# 03_-_POWER.net
KiCad netlist of a schematic drawn in Altium Designer
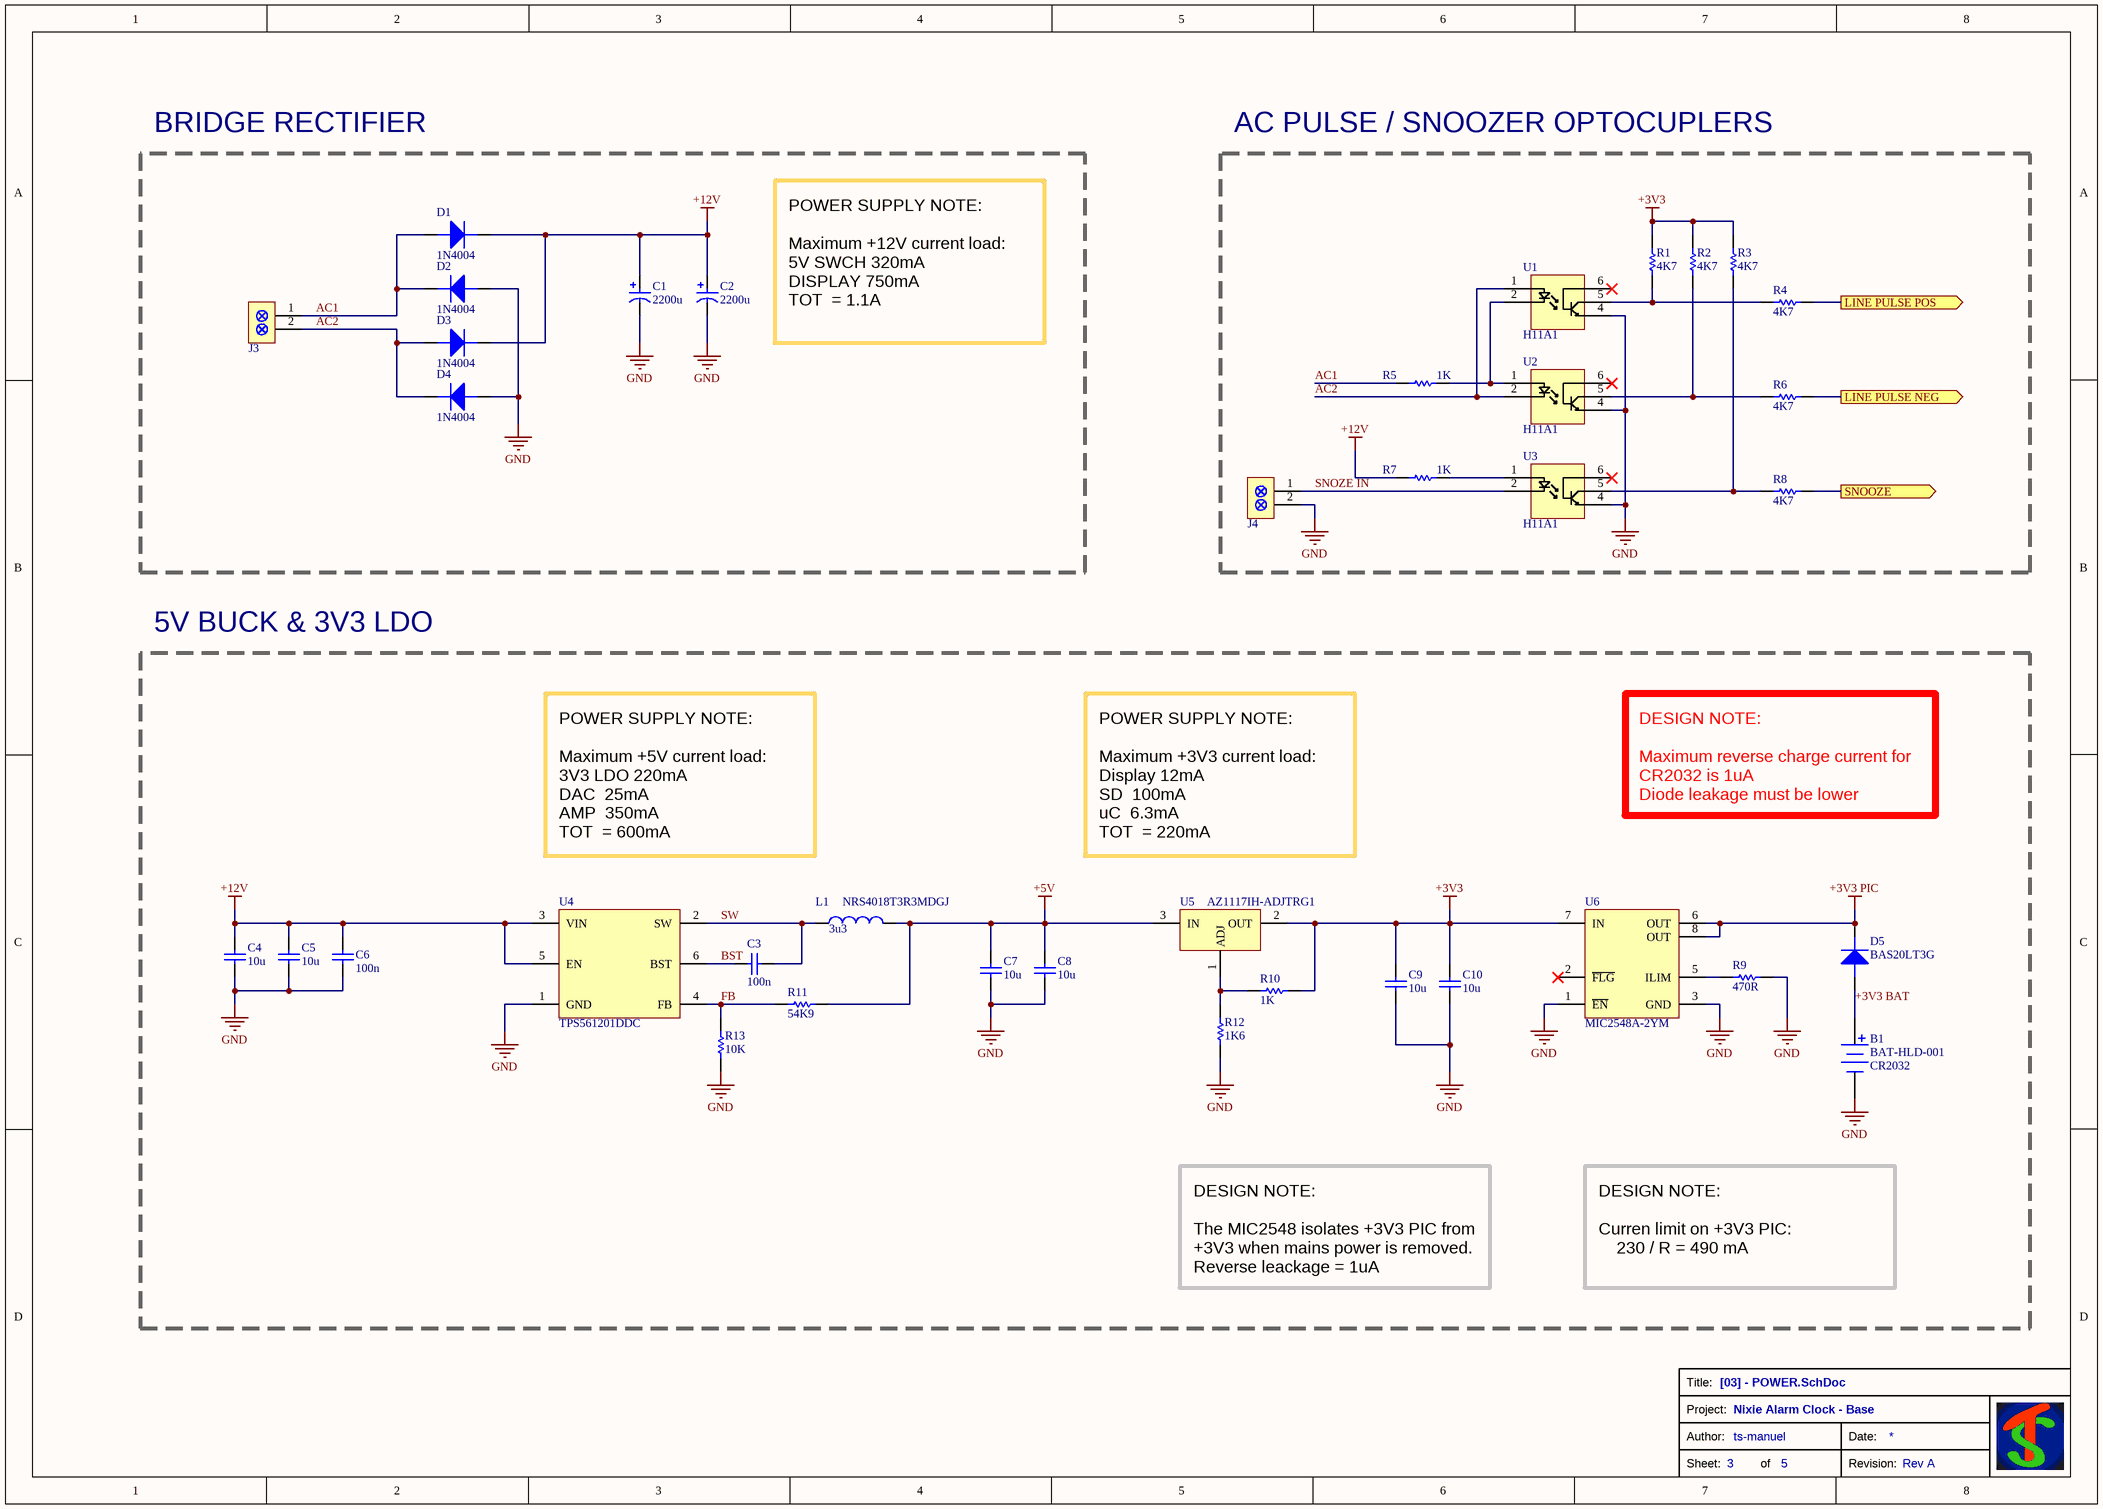
[diagram p0: [03] - POWER.SchDoc]

(export (version "E")
  (design (tool "Eeschema 10.0.6"))
  (components
    (comp (ref "B1")
      (value "BAT-HLD-001")
      (footprint "BATHLD001-CR2032")
      (description "Portabatterie a celle a bottone Linx CR2032 Battery Holder")
      (fields (field (name "SIZE") "CR2032"))
      (libsource (lib "mt_local_library") (part "CR2032-SMD-BAT-HLD-001"))
    )
    (comp (ref "C1")
      (value "2200u")
      (footprint "CAPPRD500W60D1300H2700")
      (description "ALU 25V 2200uF  RippleCurrent=1.3A 20%")
      (fields (field (name "MANUFACTURER") "KEMET") (field (name "TOLERANCE") "20%"))
      (libsource (lib "Passives") (part "CAP-RADIAL-2200u-25V-ALU-20%"))
    )
    (comp (ref "C2")
      (value "2200u")
      (footprint "CAPPRD500W60D1300H2700")
      (description "ALU 25V 2200uF  RippleCurrent=1.3A 20%")
      (fields (field (name "MANUFACTURER") "KEMET") (field (name "TOLERANCE") "20%"))
      (libsource (lib "Passives") (part "CAP-RADIAL-2200u-25V-ALU-20%"))
    )
    (comp (ref "C3")
      (value "100n")
      (footprint "CAP-0603")
      (description "MLCC - SMD 16V 100nF X7R 0603 20%")
      (fields (field (name "TOLERANCE") "20%") (field (name "MANUFACTURER") "KEMET"))
      (libsource (lib "Passives") (part "CAP-0603-100n-16V-X7R-20%"))
    )
    (comp (ref "C4")
      (value "10u")
      (footprint "CAP-0805")
      (description "MLCC - SMD 25V 10uF X5R 10%")
      (fields (field (name "MANUFACTURER") "Samsung") (field (name "TOLERANCE") "10%"))
      (libsource (lib "Passives") (part "CAP-0805-10u-25V-X5R-10%"))
    )
    (comp (ref "C5")
      (value "10u")
      (footprint "CAP-0805")
      (description "MLCC - SMD 25V 10uF X5R 10%")
      (fields (field (name "MANUFACTURER") "Samsung") (field (name "TOLERANCE") "10%"))
      (libsource (lib "Passives") (part "CAP-0805-10u-25V-X5R-10%"))
    )
    (comp (ref "C6")
      (value "100n")
      (footprint "CAP-0603")
      (description "MLCC - SMD 16V 100nF X7R 0603 20%")
      (fields (field (name "TOLERANCE") "20%") (field (name "MANUFACTURER") "KEMET"))
      (libsource (lib "Passives") (part "CAP-0603-100n-16V-X7R-20%"))
    )
    (comp (ref "C7")
      (value "10u")
      (footprint "CAP-0805")
      (description "MLCC - SMD 25V 10uF X5R 10%")
      (fields (field (name "MANUFACTURER") "Samsung") (field (name "TOLERANCE") "10%"))
      (libsource (lib "Passives") (part "CAP-0805-10u-25V-X5R-10%"))
    )
    (comp (ref "C8")
      (value "10u")
      (footprint "CAP-0805")
      (description "MLCC - SMD 25V 10uF X5R 10%")
      (fields (field (name "MANUFACTURER") "Samsung") (field (name "TOLERANCE") "10%"))
      (libsource (lib "Passives") (part "CAP-0805-10u-25V-X5R-10%"))
    )
    (comp (ref "C9")
      (value "10u")
      (footprint "CAP-0805")
      (description "MLCC - SMD 25V 10uF X5R 10%")
      (fields (field (name "MANUFACTURER") "Samsung") (field (name "TOLERANCE") "10%"))
      (libsource (lib "Passives") (part "CAP-0805-10u-25V-X5R-10%"))
    )
    (comp (ref "C10")
      (value "10u")
      (footprint "CAP-0805")
      (description "MLCC - SMD 25V 10uF X5R 10%")
      (fields (field (name "MANUFACTURER") "Samsung") (field (name "TOLERANCE") "10%"))
      (libsource (lib "Passives") (part "CAP-0805-10u-25V-X5R-10%"))
    )
    (comp (ref "D1")
      (value "1N4004")
      (footprint "DIODE-DO41")
      (description "Silicon Diode - 400V 50uA 1A")
      (libsource (lib "mt_local_library") (part "DIODE-1N4004-T"))
    )
    (comp (ref "D2")
      (value "1N4004")
      (footprint "DIODE-DO41")
      (description "Silicon Diode - 400V 50uA 1A")
      (libsource (lib "mt_local_library") (part "DIODE-1N4004-T"))
    )
    (comp (ref "D3")
      (value "1N4004")
      (footprint "DIODE-DO41")
      (description "Silicon Diode - 400V 50uA 1A")
      (libsource (lib "mt_local_library") (part "DIODE-1N4004-T"))
    )
    (comp (ref "D4")
      (value "1N4004")
      (footprint "DIODE-DO41")
      (description "Silicon Diode - 400V 50uA 1A")
      (libsource (lib "mt_local_library") (part "DIODE-1N4004-T"))
    )
    (comp (ref "D5")
      (value "BAS20LT3G")
      (footprint "SOT95P240X110-3N")
      (description "Silicon Diode - 200V 0.1uA 200mA")
      (libsource (lib "mt_local_library") (part "DIODE-BAS20LT3G"))
    )
    (comp (ref "J3")
      (value "SCREW-TH-BLOCK-200-2")
      (footprint "SCREW-TH-BLOCK-200-2")
      (description "Screw Therminal Block 200 mil Pitch 2 Contacts")
      (libsource (lib "mt_local_library") (part "SCREW-TH-BLOCK-200-2"))
    )
    (comp (ref "J4")
      (value "SCREW-TH-BLOCK-200-2")
      (footprint "SCREW-TH-BLOCK-200-2")
      (description "Screw Therminal Block 200 mil Pitch 2 Contacts")
      (libsource (lib "mt_local_library") (part "SCREW-TH-BLOCK-200-2"))
    )
    (comp (ref "L1")
      (value "NRS4018T3R3MDGJ")
      (footprint "INDP4040X18M")
      (description "Fixed Inductor 4018 3.3uH 66mOhms +/-20%Tol 2300mA")
      (fields
        (field (name "MANUFACTURER") "Taiyo Yuden")
        (field (name "TOLERANCE") "20%")
        (field (name "ALTIUM_VALUE") "3u3")
      )
      (libsource (lib "Passives") (part "IND-4018-3u3-NRS4018T3R3MDGJ"))
    )
    (comp (ref "R1")
      (value "4K7")
      (footprint "RES-0603")
      (description "Thick Film - SMD 75V 1/10W 4.7K ohm 0603 1%")
      (fields (field (name "MANUFACTURER") "Yageo") (field (name "TOLERANCE") "1%"))
      (libsource (lib "Passives") (part "RES-0603-4K7-1/10W-1%"))
    )
    (comp (ref "R2")
      (value "4K7")
      (footprint "RES-0603")
      (description "Thick Film - SMD 75V 1/10W 4.7K ohm 0603 1%")
      (fields (field (name "MANUFACTURER") "Yageo") (field (name "TOLERANCE") "1%"))
      (libsource (lib "Passives") (part "RES-0603-4K7-1/10W-1%"))
    )
    (comp (ref "R3")
      (value "4K7")
      (footprint "RES-0603")
      (description "Thick Film - SMD 75V 1/10W 4.7K ohm 0603 1%")
      (fields (field (name "MANUFACTURER") "Yageo") (field (name "TOLERANCE") "1%"))
      (libsource (lib "Passives") (part "RES-0603-4K7-1/10W-1%"))
    )
    (comp (ref "R4")
      (value "4K7")
      (footprint "RES-0603")
      (description "Thick Film - SMD 75V 1/10W 4.7K ohm 0603 1%")
      (fields (field (name "MANUFACTURER") "Yageo") (field (name "TOLERANCE") "1%"))
      (libsource (lib "Passives") (part "RES-0603-4K7-1/10W-1%"))
    )
    (comp (ref "R5")
      (value "1K")
      (footprint "RES-0805")
      (description "Thick Film - SMD 150V 1/8W 1K ohm 0805 1%")
      (fields (field (name "MANUFACTURER") "Yageo") (field (name "TOLERANCE") "1%"))
      (libsource (lib "Passives") (part "RES-0805-1K-1/8W-1%"))
    )
    (comp (ref "R6")
      (value "4K7")
      (footprint "RES-0603")
      (description "Thick Film - SMD 75V 1/10W 4.7K ohm 0603 1%")
      (fields (field (name "MANUFACTURER") "Yageo") (field (name "TOLERANCE") "1%"))
      (libsource (lib "Passives") (part "RES-0603-4K7-1/10W-1%"))
    )
    (comp (ref "R7")
      (value "1K")
      (footprint "RES-0805")
      (description "Thick Film - SMD 150V 1/8W 1K ohm 0805 1%")
      (fields (field (name "MANUFACTURER") "Yageo") (field (name "TOLERANCE") "1%"))
      (libsource (lib "Passives") (part "RES-0805-1K-1/8W-1%"))
    )
    (comp (ref "R8")
      (value "4K7")
      (footprint "RES-0603")
      (description "Thick Film - SMD 75V 1/10W 4.7K ohm 0603 1%")
      (fields (field (name "MANUFACTURER") "Yageo") (field (name "TOLERANCE") "1%"))
      (libsource (lib "Passives") (part "RES-0603-4K7-1/10W-1%"))
    )
    (comp (ref "R9")
      (value "470R")
      (footprint "RES-0603")
      (description "Thick Film - SMD 75V 1/10W 470 ohm 0603 1%")
      (fields (field (name "MANUFACTURER") "Yageo") (field (name "TOLERANCE") "1%"))
      (libsource (lib "Passives") (part "RES-0603-470-1/10W-1%"))
    )
    (comp (ref "R10")
      (value "1K")
      (footprint "RES-0603")
      (description "Thick Film - SMD 75V 1/10W 1K ohm 0603 1%")
      (fields (field (name "MANUFACTURER") "Yageo") (field (name "TOLERANCE") "1%"))
      (libsource (lib "Passives") (part "RES-0603-1K-1/10W-1%"))
    )
    (comp (ref "R11")
      (value "54K9")
      (footprint "RES-0603")
      (description "Thick Film - SMD 75V 1/10W 54.9K ohm 0603 1%")
      (fields (field (name "MANUFACTURER") "Yageo") (field (name "TOLERANCE") "1%"))
      (libsource (lib "Passives") (part "RES-0603-54K9-1/10W-1%"))
    )
    (comp (ref "R12")
      (value "1K6")
      (footprint "RES-0603")
      (description "Thick Film - SMD 75V 1/10W 1.6K ohm 0603 1%")
      (fields (field (name "MANUFACTURER") "Yageo") (field (name "TOLERANCE") "1%"))
      (libsource (lib "Passives") (part "RES-0603-1K6-1/10W-1%"))
    )
    (comp (ref "R13")
      (value "10K")
      (footprint "RES-0603")
      (description "Thick Film - SMD 75V 1/10W 10K ohm 0603 1%")
      (fields (field (name "MANUFACTURER") "Yageo") (field (name "TOLERANCE") "1%"))
      (libsource (lib "Passives") (part "RES-0603-10K-1/10W-1%"))
    )
    (comp (ref "U1")
      (value "H11A1")
      (footprint "DIP762W51P254L889H508Q6N")
      (description "Optocoupler, Phototransistor Output, With Base Connection")
      (libsource (lib "mt_local_library") (part "OPTO-TH-H11A1"))
    )
    (comp (ref "U2")
      (value "H11A1")
      (footprint "DIP762W51P254L889H508Q6N")
      (description "Optocoupler, Phototransistor Output, With Base Connection")
      (libsource (lib "mt_local_library") (part "OPTO-TH-H11A1"))
    )
    (comp (ref "U3")
      (value "H11A1")
      (footprint "DIP762W51P254L889H508Q6N")
      (description "Optocoupler, Phototransistor Output, With Base Connection")
      (libsource (lib "mt_local_library") (part "OPTO-TH-H11A1"))
    )
    (comp (ref "U4")
      (value "TPS561201DDC")
      (footprint "SOT95P278X110-6N")
      (description "4.5-V to 17-V Input, 1-A Synchronous Step-Down Voltage Regulator")
      (libsource (lib "mt_local_library") (part "TPS561201DDC"))
    )
    (comp (ref "U5")
      (value "AZ1117IH-ADJTRG1")
      (footprint "SOT230P700X180-4M")
      (description "LDO 15V Max 1.2V Dropout 1.35A Max")
      (libsource (lib "mt_local_library") (part "LDO-AZ1117IH-ADJ"))
    )
    (comp (ref "U6")
      (value "MIC2548A-2YM")
      (footprint "SOIC127P600X175-8N")
      (description "Programmable Current-Limit High-Side Switch")
      (libsource (lib "mt_local_library") (part "MIC2548A-2YM"))
    )
  )
  (nets
    (net (code "1") (name "+3V3") (class "Default")
      (node (ref "C10") (pin "1") (pinfunction "1_1") (pintype "passive"))
      (node (ref "C9") (pin "1") (pinfunction "1_1") (pintype "passive"))
      (node (ref "R1") (pin "2") (pinfunction "2_2") (pintype "passive"))
      (node (ref "R10") (pin "2") (pinfunction "2_2") (pintype "passive"))
      (node (ref "R2") (pin "2") (pinfunction "2_2") (pintype "passive"))
      (node (ref "R3") (pin "2") (pinfunction "2_2") (pintype "passive"))
      (node (ref "U5") (pin "2") (pinfunction "OUT_2") (pintype "passive"))
      (node (ref "U6") (pin "7") (pinfunction "IN_7") (pintype "power_in"))
    )
    (net (code "2") (name "+3V3 PIC") (class "Default")
      (node (ref "D5") (pin "3") (pinfunction "C_3") (pintype "passive"))
      (node (ref "U6") (pin "6") (pinfunction "OUT_6") (pintype "passive"))
      (node (ref "U6") (pin "8") (pinfunction "OUT_8") (pintype "passive"))
    )
    (net (code "3") (name "+5V") (class "Default")
      (node (ref "C7") (pin "1") (pinfunction "1_1") (pintype "passive"))
      (node (ref "C8") (pin "1") (pinfunction "1_1") (pintype "passive"))
      (node (ref "L1") (pin "2") (pinfunction "2_2") (pintype "passive"))
      (node (ref "R11") (pin "2") (pinfunction "2_2") (pintype "passive"))
      (node (ref "U5") (pin "3") (pinfunction "IN_3") (pintype "passive"))
    )
    (net (code "4") (name "+12V") (class "Default")
      (node (ref "C1") (pin "1") (pinfunction "P_1") (pintype "passive"))
      (node (ref "C2") (pin "1") (pinfunction "P_1") (pintype "passive"))
      (node (ref "C4") (pin "1") (pinfunction "1_1") (pintype "passive"))
      (node (ref "C5") (pin "1") (pinfunction "1_1") (pintype "passive"))
      (node (ref "C6") (pin "1") (pinfunction "1_1") (pintype "passive"))
      (node (ref "D1") (pin "K") (pinfunction "C_K") (pintype "passive"))
      (node (ref "D3") (pin "K") (pinfunction "C_K") (pintype "passive"))
      (node (ref "R7") (pin "2") (pinfunction "2_2") (pintype "passive"))
      (node (ref "U4") (pin "3") (pinfunction "VIN_3") (pintype "power_in"))
      (node (ref "U4") (pin "5") (pinfunction "EN_5") (pintype "passive"))
    )
    (net (code "5") (name "/+3V3 BAT") (class "Default")
      (node (ref "B1") (pin "1") (pinfunction "+_1") (pintype "passive"))
      (node (ref "D5") (pin "1") (pinfunction "A_1") (pintype "passive"))
    )
    (net (code "6") (name "/AC1") (class "Default")
      (node (ref "D1") (pin "A") (pinfunction "A_A") (pintype "passive"))
      (node (ref "D2") (pin "K") (pinfunction "C_K") (pintype "passive"))
      (node (ref "J3") (pin "1") (pinfunction "1_1") (pintype "passive"))
      (node (ref "R5") (pin "2") (pinfunction "2_2") (pintype "passive"))
    )
    (net (code "7") (name "/AC2") (class "Default")
      (node (ref "D3") (pin "A") (pinfunction "A_A") (pintype "passive"))
      (node (ref "D4") (pin "K") (pinfunction "C_K") (pintype "passive"))
      (node (ref "J3") (pin "2") (pinfunction "2_2") (pintype "passive"))
      (node (ref "U1") (pin "1") (pinfunction "A_1") (pintype "passive"))
      (node (ref "U2") (pin "2") (pinfunction "K_2") (pintype "passive"))
    )
    (net (code "8") (name "/BST") (class "Default")
      (node (ref "C3") (pin "2") (pinfunction "2_2") (pintype "passive"))
      (node (ref "U4") (pin "6") (pinfunction "BST_6") (pintype "passive"))
    )
    (net (code "9") (name "/FB") (class "Default")
      (node (ref "R11") (pin "1") (pinfunction "1_1") (pintype "passive"))
      (node (ref "R13") (pin "2") (pinfunction "2_2") (pintype "passive"))
      (node (ref "U4") (pin "4") (pinfunction "FB_4") (pintype "passive"))
    )
    (net (code "10") (name "/LINE PULSE NEG") (class "Default")
      (node (ref "R6") (pin "1") (pinfunction "1_1") (pintype "passive"))
    )
    (net (code "11") (name "/LINE PULSE POS") (class "Default")
      (node (ref "R4") (pin "1") (pinfunction "1_1") (pintype "passive"))
    )
    (net (code "12") (name "/SNOOZE") (class "Default")
      (node (ref "R8") (pin "1") (pinfunction "1_1") (pintype "passive"))
    )
    (net (code "13") (name "/SNOZE IN") (class "Default")
      (node (ref "J4") (pin "1") (pinfunction "1_1") (pintype "passive"))
      (node (ref "U3") (pin "2") (pinfunction "K_2") (pintype "passive"))
    )
    (net (code "14") (name "/SW") (class "Default")
      (node (ref "C3") (pin "1") (pinfunction "1_1") (pintype "passive"))
      (node (ref "L1") (pin "1") (pinfunction "1_1") (pintype "passive"))
      (node (ref "U4") (pin "2") (pinfunction "SW_2") (pintype "passive"))
    )
    (net (code "15") (name "GND") (class "Default")
      (node (ref "B1") (pin "2") (pinfunction "-_2") (pintype "passive"))
      (node (ref "C1") (pin "2") (pinfunction "N_2") (pintype "passive"))
      (node (ref "C10") (pin "2") (pinfunction "2_2") (pintype "passive"))
      (node (ref "C2") (pin "2") (pinfunction "N_2") (pintype "passive"))
      (node (ref "C4") (pin "2") (pinfunction "2_2") (pintype "passive"))
      (node (ref "C5") (pin "2") (pinfunction "2_2") (pintype "passive"))
      (node (ref "C6") (pin "2") (pinfunction "2_2") (pintype "passive"))
      (node (ref "C7") (pin "2") (pinfunction "2_2") (pintype "passive"))
      (node (ref "C8") (pin "2") (pinfunction "2_2") (pintype "passive"))
      (node (ref "C9") (pin "2") (pinfunction "2_2") (pintype "passive"))
      (node (ref "D2") (pin "A") (pinfunction "A_A") (pintype "passive"))
      (node (ref "D4") (pin "A") (pinfunction "A_A") (pintype "passive"))
      (node (ref "J4") (pin "2") (pinfunction "2_2") (pintype "passive"))
      (node (ref "R12") (pin "1") (pinfunction "1_1") (pintype "passive"))
      (node (ref "R13") (pin "1") (pinfunction "1_1") (pintype "passive"))
      (node (ref "R9") (pin "2") (pinfunction "2_2") (pintype "passive"))
      (node (ref "U1") (pin "4") (pinfunction "E_4") (pintype "passive"))
      (node (ref "U2") (pin "4") (pinfunction "E_4") (pintype "passive"))
      (node (ref "U3") (pin "4") (pinfunction "E_4") (pintype "passive"))
      (node (ref "U4") (pin "1") (pinfunction "GND_1") (pintype "power_in"))
      (node (ref "U6") (pin "1") (pinfunction "~{EN}_1") (pintype "passive"))
      (node (ref "U6") (pin "3") (pinfunction "GND_3") (pintype "passive"))
    )
    (net (code "16") (name "Net-(U1-C)") (class "Default")
      (node (ref "R1") (pin "1") (pinfunction "1_1") (pintype "passive"))
      (node (ref "R4") (pin "2") (pinfunction "2_2") (pintype "passive"))
      (node (ref "U1") (pin "5") (pinfunction "C_5") (pintype "passive"))
    )
    (net (code "17") (name "Net-(U1-K)") (class "Default")
      (node (ref "R5") (pin "1") (pinfunction "1_1") (pintype "passive"))
      (node (ref "U1") (pin "2") (pinfunction "K_2") (pintype "passive"))
      (node (ref "U2") (pin "1") (pinfunction "A_1") (pintype "passive"))
    )
    (net (code "18") (name "Net-(U2-C)") (class "Default")
      (node (ref "R2") (pin "1") (pinfunction "1_1") (pintype "passive"))
      (node (ref "R6") (pin "2") (pinfunction "2_2") (pintype "passive"))
      (node (ref "U2") (pin "5") (pinfunction "C_5") (pintype "passive"))
    )
    (net (code "19") (name "Net-(U3-A)") (class "Default")
      (node (ref "R7") (pin "1") (pinfunction "1_1") (pintype "passive"))
      (node (ref "U3") (pin "1") (pinfunction "A_1") (pintype "passive"))
    )
    (net (code "20") (name "Net-(U3-C)") (class "Default")
      (node (ref "R3") (pin "1") (pinfunction "1_1") (pintype "passive"))
      (node (ref "R8") (pin "2") (pinfunction "2_2") (pintype "passive"))
      (node (ref "U3") (pin "5") (pinfunction "C_5") (pintype "passive"))
    )
    (net (code "21") (name "Net-(U5-ADJ)") (class "Default")
      (node (ref "R10") (pin "1") (pinfunction "1_1") (pintype "passive"))
      (node (ref "R12") (pin "2") (pinfunction "2_2") (pintype "passive"))
      (node (ref "U5") (pin "1") (pinfunction "ADJ_1") (pintype "passive"))
    )
    (net (code "22") (name "Net-(U6-ILIM)") (class "Default")
      (node (ref "R9") (pin "1") (pinfunction "1_1") (pintype "passive"))
      (node (ref "U6") (pin "5") (pinfunction "ILIM_5") (pintype "passive"))
    )
    (net (code "23") (name "unconnected-(U1-B-Pad6)") (class "Default")
      (node (ref "U1") (pin "6") (pinfunction "B_6") (pintype "passive+no_connect"))
    )
    (net (code "24") (name "unconnected-(U2-B-Pad6)") (class "Default")
      (node (ref "U2") (pin "6") (pinfunction "B_6") (pintype "passive+no_connect"))
    )
    (net (code "25") (name "unconnected-(U3-B-Pad6)") (class "Default")
      (node (ref "U3") (pin "6") (pinfunction "B_6") (pintype "passive+no_connect"))
    )
    (net (code "26") (name "unconnected-(U6-~{FLG}-Pad2)") (class "Default")
      (node (ref "U6") (pin "2") (pinfunction "~{FLG}_2") (pintype "open_collector+no_connect"))
    )
  )
)
